# PIC32Circuit.net
KiCad netlist of a schematic drawn in EAGLE
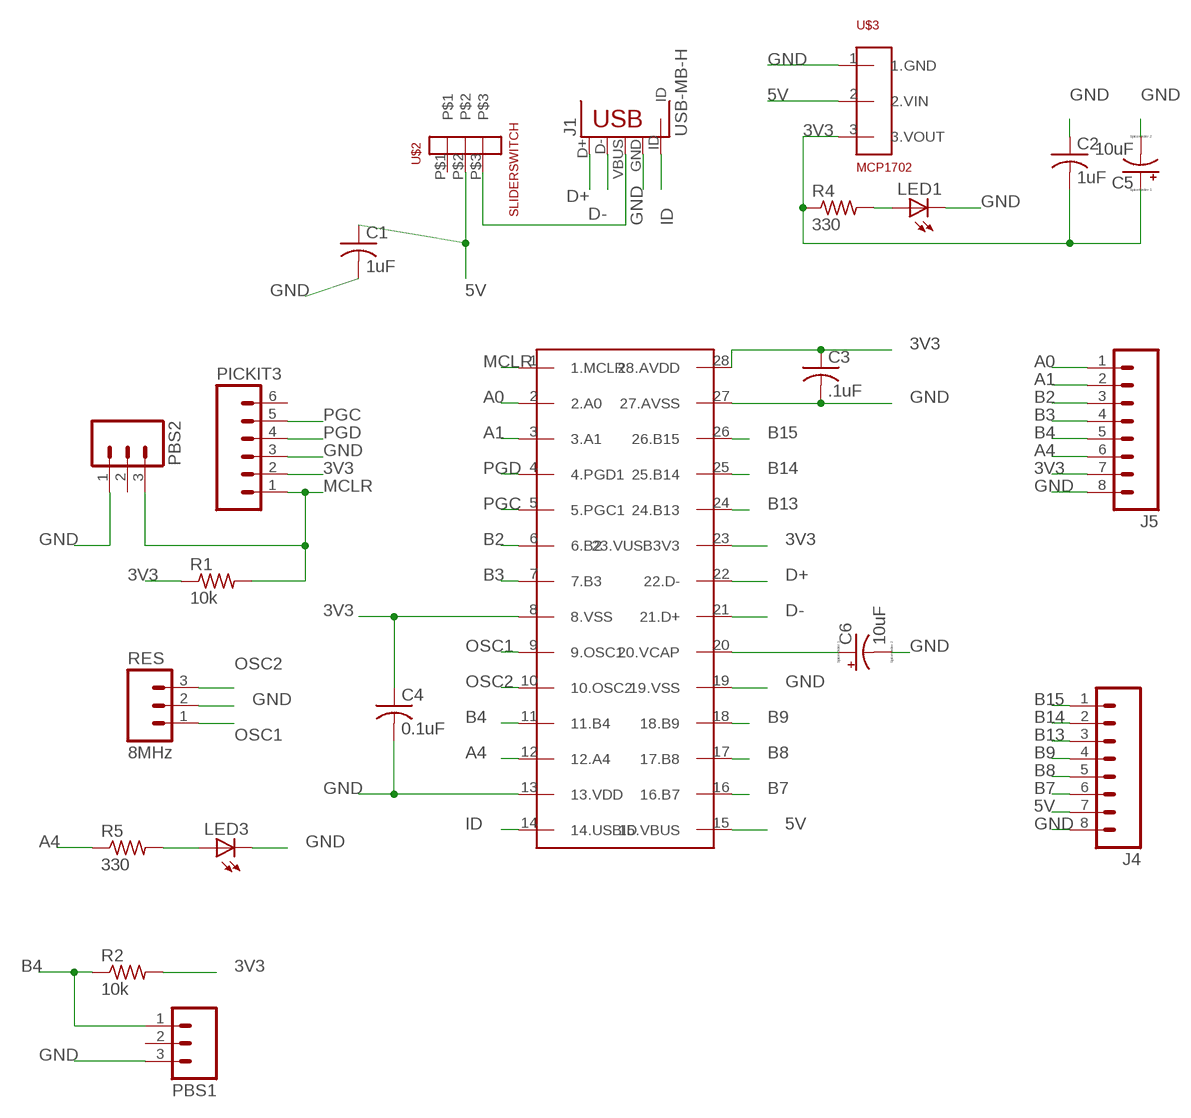
[diagram p0: schematic, sheet 1]

(export (version "E")
  (design (tool "Eeschema 10.0.6"))
  (components
    (comp (ref "C1")
      (value "1uF")
      (footprint "eagle-import:C025-024X044")
      (libsource (lib "eagle-import") (part "C-US025-024X044"))
    )
    (comp (ref "C2")
      (value "1uF")
      (footprint "eagle-import:C025-024X044")
      (libsource (lib "eagle-import") (part "C-US025-024X044"))
    )
    (comp (ref "C3")
      (value ".1uF")
      (footprint "eagle-import:C025-024X044")
      (libsource (lib "eagle-import") (part "C-US025-024X044"))
    )
    (comp (ref "C4")
      (value "0.1uF")
      (footprint "eagle-import:C025-024X044")
      (libsource (lib "eagle-import") (part "C-US025-024X044"))
    )
    (comp (ref "C5")
      (value "10uF")
      (footprint "eagle-import:TT2D4")
      (libsource (lib "eagle-import") (part "CPOL-USTT2D4"))
    )
    (comp (ref "C6")
      (value "10uF")
      (footprint "eagle-import:TT2D4")
      (libsource (lib "eagle-import") (part "CPOL-USTT2D4"))
    )
    (comp (ref "J1")
      (value "USB-MB-H")
      (footprint "eagle-import:USB-MB-H")
      (libsource (lib "eagle-import") (part "USB-MB-H"))
    )
    (comp (ref "J4")
      (value "M08")
      (footprint "eagle-import:1X08_ROUND")
      (libsource (lib "eagle-import") (part "M08"))
    )
    (comp (ref "J5")
      (value "M08")
      (footprint "eagle-import:1X08_ROUND")
      (libsource (lib "eagle-import") (part "M08"))
    )
    (comp (ref "LED1")
      (value "LED3MM")
      (footprint "eagle-import:LED3MM")
      (libsource (lib "eagle-import") (part "LED3MM"))
    )
    (comp (ref "LED3")
      (value "LED3MM")
      (footprint "eagle-import:LED3MM")
      (libsource (lib "eagle-import") (part "LED3MM"))
    )
    (comp (ref "PBS1")
      (value "M03PTH")
      (footprint "eagle-import:1X03")
      (libsource (lib "eagle-import") (part "M03PTH"))
    )
    (comp (ref "PBS2")
      (value "M03PTH")
      (footprint "eagle-import:1X03")
      (libsource (lib "eagle-import") (part "M03PTH"))
    )
    (comp (ref "PICKIT3")
      (value "M06SILK_FEMALE_PTH")
      (footprint "eagle-import:1X06")
      (libsource (lib "eagle-import") (part "M06SILK_FEMALE_PTH"))
    )
    (comp (ref "R1")
      (value "10k")
      (footprint "eagle-import:0207_10")
      (libsource (lib "eagle-import") (part "R-US_0207/10"))
    )
    (comp (ref "R2")
      (value "10k")
      (footprint "eagle-import:0207_10")
      (libsource (lib "eagle-import") (part "R-US_0207/10"))
    )
    (comp (ref "R4")
      (value "330")
      (footprint "eagle-import:0207_10")
      (libsource (lib "eagle-import") (part "R-US_0207/10"))
    )
    (comp (ref "R5")
      (value "330")
      (footprint "eagle-import:0207_10")
      (libsource (lib "eagle-import") (part "R-US_0207/10"))
    )
    (comp (ref "RES")
      (value "8MHz")
      (footprint "eagle-import:1X03")
      (libsource (lib "eagle-import") (part "M03PTH"))
    )
    (comp (ref "U$1")
      (value "PIC32MX250F128B")
      (footprint "eagle-import:DIL28-3")
      (libsource (lib "eagle-import") (part "PIC32MX250F128B"))
    )
    (comp (ref "U$2")
      (value "SLIDERSWITCH")
      (footprint "eagle-import:SLIDERSWITCH")
      (libsource (lib "eagle-import") (part "SLIDERSWITCH"))
    )
    (comp (ref "U$3")
      (value "MCP1702")
      (footprint "eagle-import:TO92")
      (libsource (lib "eagle-import") (part "MCP1702"))
    )
  )
  (nets
    (net (code "1") (name "/3V3") (class "Default")
      (node (ref "C2") (pin "2") (pinfunction "2_2") (pintype "passive"))
      (node (ref "C3") (pin "1") (pinfunction "1_1") (pintype "passive"))
      (node (ref "C4") (pin "1") (pinfunction "1_1") (pintype "passive"))
      (node (ref "C5") (pin "+") (pinfunction "+_+") (pintype "passive"))
      (node (ref "J5") (pin "7") (pinfunction "7_7") (pintype "passive"))
      (node (ref "PICKIT3") (pin "2") (pinfunction "2_2") (pintype "passive"))
      (node (ref "R1") (pin "1") (pinfunction "1_1") (pintype "passive"))
      (node (ref "R2") (pin "2") (pinfunction "2_2") (pintype "passive"))
      (node (ref "R4") (pin "1") (pinfunction "1_1") (pintype "passive"))
      (node (ref "U$1") (pin "23") (pinfunction "23.VUSB3V3_23") (pintype "bidirectional"))
      (node (ref "U$1") (pin "28") (pinfunction "28.AVDD_28") (pintype "bidirectional"))
      (node (ref "U$1") (pin "8") (pinfunction "8.VSS_8") (pintype "bidirectional"))
      (node (ref "U$3") (pin "3") (pinfunction "3.VOUT_3") (pintype "bidirectional"))
    )
    (net (code "2") (name "/5V") (class "Default")
      (node (ref "C1") (pin "1") (pinfunction "1_1") (pintype "passive"))
      (node (ref "J4") (pin "7") (pinfunction "7_7") (pintype "passive"))
      (node (ref "U$1") (pin "15") (pinfunction "15.VBUS_15") (pintype "bidirectional"))
      (node (ref "U$2") (pin "P$2") (pinfunction "P$2_P$2") (pintype "bidirectional"))
      (node (ref "U$3") (pin "2") (pinfunction "2.VIN_2") (pintype "bidirectional"))
    )
    (net (code "3") (name "/A0") (class "Default")
      (node (ref "J5") (pin "1") (pinfunction "1_1") (pintype "passive"))
      (node (ref "U$1") (pin "2") (pinfunction "2.A0_2") (pintype "bidirectional"))
    )
    (net (code "4") (name "/A1") (class "Default")
      (node (ref "J5") (pin "2") (pinfunction "2_2") (pintype "passive"))
      (node (ref "U$1") (pin "3") (pinfunction "3.A1_3") (pintype "bidirectional"))
    )
    (net (code "5") (name "/A4") (class "Default")
      (node (ref "J5") (pin "6") (pinfunction "6_6") (pintype "passive"))
      (node (ref "R5") (pin "1") (pinfunction "1_1") (pintype "passive"))
      (node (ref "U$1") (pin "12") (pinfunction "12.A4_12") (pintype "bidirectional"))
    )
    (net (code "6") (name "/B2") (class "Default")
      (node (ref "J5") (pin "3") (pinfunction "3_3") (pintype "passive"))
      (node (ref "U$1") (pin "6") (pinfunction "6.B2_6") (pintype "bidirectional"))
    )
    (net (code "7") (name "/B3") (class "Default")
      (node (ref "J5") (pin "4") (pinfunction "4_4") (pintype "passive"))
      (node (ref "U$1") (pin "7") (pinfunction "7.B3_7") (pintype "bidirectional"))
    )
    (net (code "8") (name "/B4") (class "Default")
      (node (ref "J5") (pin "5") (pinfunction "5_5") (pintype "passive"))
      (node (ref "PBS1") (pin "1") (pinfunction "1_1") (pintype "passive"))
      (node (ref "R2") (pin "1") (pinfunction "1_1") (pintype "passive"))
      (node (ref "U$1") (pin "11") (pinfunction "11.B4_11") (pintype "bidirectional"))
    )
    (net (code "9") (name "/B7") (class "Default")
      (node (ref "J4") (pin "6") (pinfunction "6_6") (pintype "passive"))
      (node (ref "U$1") (pin "16") (pinfunction "16.B7_16") (pintype "bidirectional"))
    )
    (net (code "10") (name "/B8") (class "Default")
      (node (ref "J4") (pin "5") (pinfunction "5_5") (pintype "passive"))
      (node (ref "U$1") (pin "17") (pinfunction "17.B8_17") (pintype "bidirectional"))
    )
    (net (code "11") (name "/B9") (class "Default")
      (node (ref "J4") (pin "4") (pinfunction "4_4") (pintype "passive"))
      (node (ref "U$1") (pin "18") (pinfunction "18.B9_18") (pintype "bidirectional"))
    )
    (net (code "12") (name "/B13") (class "Default")
      (node (ref "J4") (pin "3") (pinfunction "3_3") (pintype "passive"))
      (node (ref "U$1") (pin "24") (pinfunction "24.B13_24") (pintype "bidirectional"))
    )
    (net (code "13") (name "/B14") (class "Default")
      (node (ref "J4") (pin "2") (pinfunction "2_2") (pintype "passive"))
      (node (ref "U$1") (pin "25") (pinfunction "25.B14_25") (pintype "bidirectional"))
    )
    (net (code "14") (name "/B15") (class "Default")
      (node (ref "J4") (pin "1") (pinfunction "1_1") (pintype "passive"))
      (node (ref "U$1") (pin "26") (pinfunction "26.B15_26") (pintype "bidirectional"))
    )
    (net (code "15") (name "/D+") (class "Default")
      (node (ref "J1") (pin "D+") (pinfunction "D+_D+") (pintype "bidirectional"))
      (node (ref "U$1") (pin "22") (pinfunction "22.D-_22") (pintype "bidirectional"))
    )
    (net (code "16") (name "/D-") (class "Default")
      (node (ref "J1") (pin "D-") (pinfunction "D-_D-") (pintype "bidirectional"))
      (node (ref "U$1") (pin "21") (pinfunction "21.D+_21") (pintype "bidirectional"))
    )
    (net (code "17") (name "/GND") (class "Default")
      (node (ref "C1") (pin "2") (pinfunction "2_2") (pintype "passive"))
      (node (ref "C2") (pin "1") (pinfunction "1_1") (pintype "passive"))
      (node (ref "C3") (pin "2") (pinfunction "2_2") (pintype "passive"))
      (node (ref "C4") (pin "2") (pinfunction "2_2") (pintype "passive"))
      (node (ref "C5") (pin "-") (pinfunction "-_-") (pintype "passive"))
      (node (ref "C6") (pin "-") (pinfunction "-_-") (pintype "passive"))
      (node (ref "J1") (pin "GND") (pinfunction "GND_GND") (pintype "bidirectional"))
      (node (ref "J4") (pin "8") (pinfunction "8_8") (pintype "passive"))
      (node (ref "J5") (pin "8") (pinfunction "8_8") (pintype "passive"))
      (node (ref "LED1") (pin "K") (pinfunction "C_K") (pintype "passive"))
      (node (ref "LED3") (pin "K") (pinfunction "C_K") (pintype "passive"))
      (node (ref "PBS1") (pin "3") (pinfunction "3_3") (pintype "passive"))
      (node (ref "PBS2") (pin "1") (pinfunction "1_1") (pintype "passive"))
      (node (ref "PICKIT3") (pin "3") (pinfunction "3_3") (pintype "passive"))
      (node (ref "RES") (pin "2") (pinfunction "2_2") (pintype "passive"))
      (node (ref "U$1") (pin "13") (pinfunction "13.VDD_13") (pintype "bidirectional"))
      (node (ref "U$1") (pin "19") (pinfunction "19.VSS_19") (pintype "bidirectional"))
      (node (ref "U$1") (pin "27") (pinfunction "27.AVSS_27") (pintype "bidirectional"))
      (node (ref "U$3") (pin "1") (pinfunction "1.GND_1") (pintype "bidirectional"))
    )
    (net (code "18") (name "/ID") (class "Default")
      (node (ref "J1") (pin "ID") (pinfunction "ID_ID") (pintype "bidirectional"))
      (node (ref "U$1") (pin "14") (pinfunction "14.USBID_14") (pintype "bidirectional"))
    )
    (net (code "19") (name "/MCLR") (class "Default")
      (node (ref "PBS2") (pin "3") (pinfunction "3_3") (pintype "passive"))
      (node (ref "PICKIT3") (pin "1") (pinfunction "1_1") (pintype "passive"))
      (node (ref "R1") (pin "2") (pinfunction "2_2") (pintype "passive"))
      (node (ref "U$1") (pin "1") (pinfunction "1.MCLR_1") (pintype "bidirectional"))
    )
    (net (code "20") (name "/OSC1") (class "Default")
      (node (ref "RES") (pin "1") (pinfunction "1_1") (pintype "passive"))
      (node (ref "U$1") (pin "9") (pinfunction "9.OSC1_9") (pintype "bidirectional"))
    )
    (net (code "21") (name "/OSC2") (class "Default")
      (node (ref "RES") (pin "3") (pinfunction "3_3") (pintype "passive"))
      (node (ref "U$1") (pin "10") (pinfunction "10.OSC2_10") (pintype "bidirectional"))
    )
    (net (code "22") (name "/PGC") (class "Default")
      (node (ref "PICKIT3") (pin "5") (pinfunction "5_5") (pintype "passive"))
      (node (ref "U$1") (pin "5") (pinfunction "5.PGC1_5") (pintype "bidirectional"))
    )
    (net (code "23") (name "/PGD") (class "Default")
      (node (ref "PICKIT3") (pin "4") (pinfunction "4_4") (pintype "passive"))
      (node (ref "U$1") (pin "4") (pinfunction "4.PGD1_4") (pintype "bidirectional"))
    )
    (net (code "24") (name "Net-(J1-PadVBUS)") (class "Default")
      (node (ref "J1") (pin "VBUS") (pinfunction "VBUS_VBUS") (pintype "bidirectional"))
      (node (ref "U$2") (pin "P$3") (pinfunction "P$3_P$3") (pintype "bidirectional"))
    )
    (net (code "25") (name "Net-(LED1-PadA)") (class "Default")
      (node (ref "LED1") (pin "A") (pinfunction "A_A") (pintype "passive"))
      (node (ref "R4") (pin "2") (pinfunction "2_2") (pintype "passive"))
    )
    (net (code "26") (name "Net-(LED3-PadA)") (class "Default")
      (node (ref "LED3") (pin "A") (pinfunction "A_A") (pintype "passive"))
      (node (ref "R5") (pin "2") (pinfunction "2_2") (pintype "passive"))
    )
    (net (code "27") (name "Net-(U$1-20.VCAP)") (class "Default")
      (node (ref "C6") (pin "+") (pinfunction "+_+") (pintype "passive"))
      (node (ref "U$1") (pin "20") (pinfunction "20.VCAP_20") (pintype "bidirectional"))
    )
    (net (code "28") (name "unconnected-(PBS1-Pad2)") (class "Default")
      (node (ref "PBS1") (pin "2") (pinfunction "2_2") (pintype "passive"))
    )
    (net (code "29") (name "unconnected-(PBS2-Pad2)") (class "Default")
      (node (ref "PBS2") (pin "2") (pinfunction "2_2") (pintype "passive"))
    )
    (net (code "30") (name "unconnected-(PICKIT3-Pad6)") (class "Default")
      (node (ref "PICKIT3") (pin "6") (pinfunction "6_6") (pintype "passive"))
    )
    (net (code "31") (name "unconnected-(U$2-PadP$1)") (class "Default")
      (node (ref "U$2") (pin "P$1") (pinfunction "P$1_P$1") (pintype "bidirectional"))
    )
  )
)
